# Z05_C8V_03.net
KiCad netlist of a schematic drawn in EAGLE
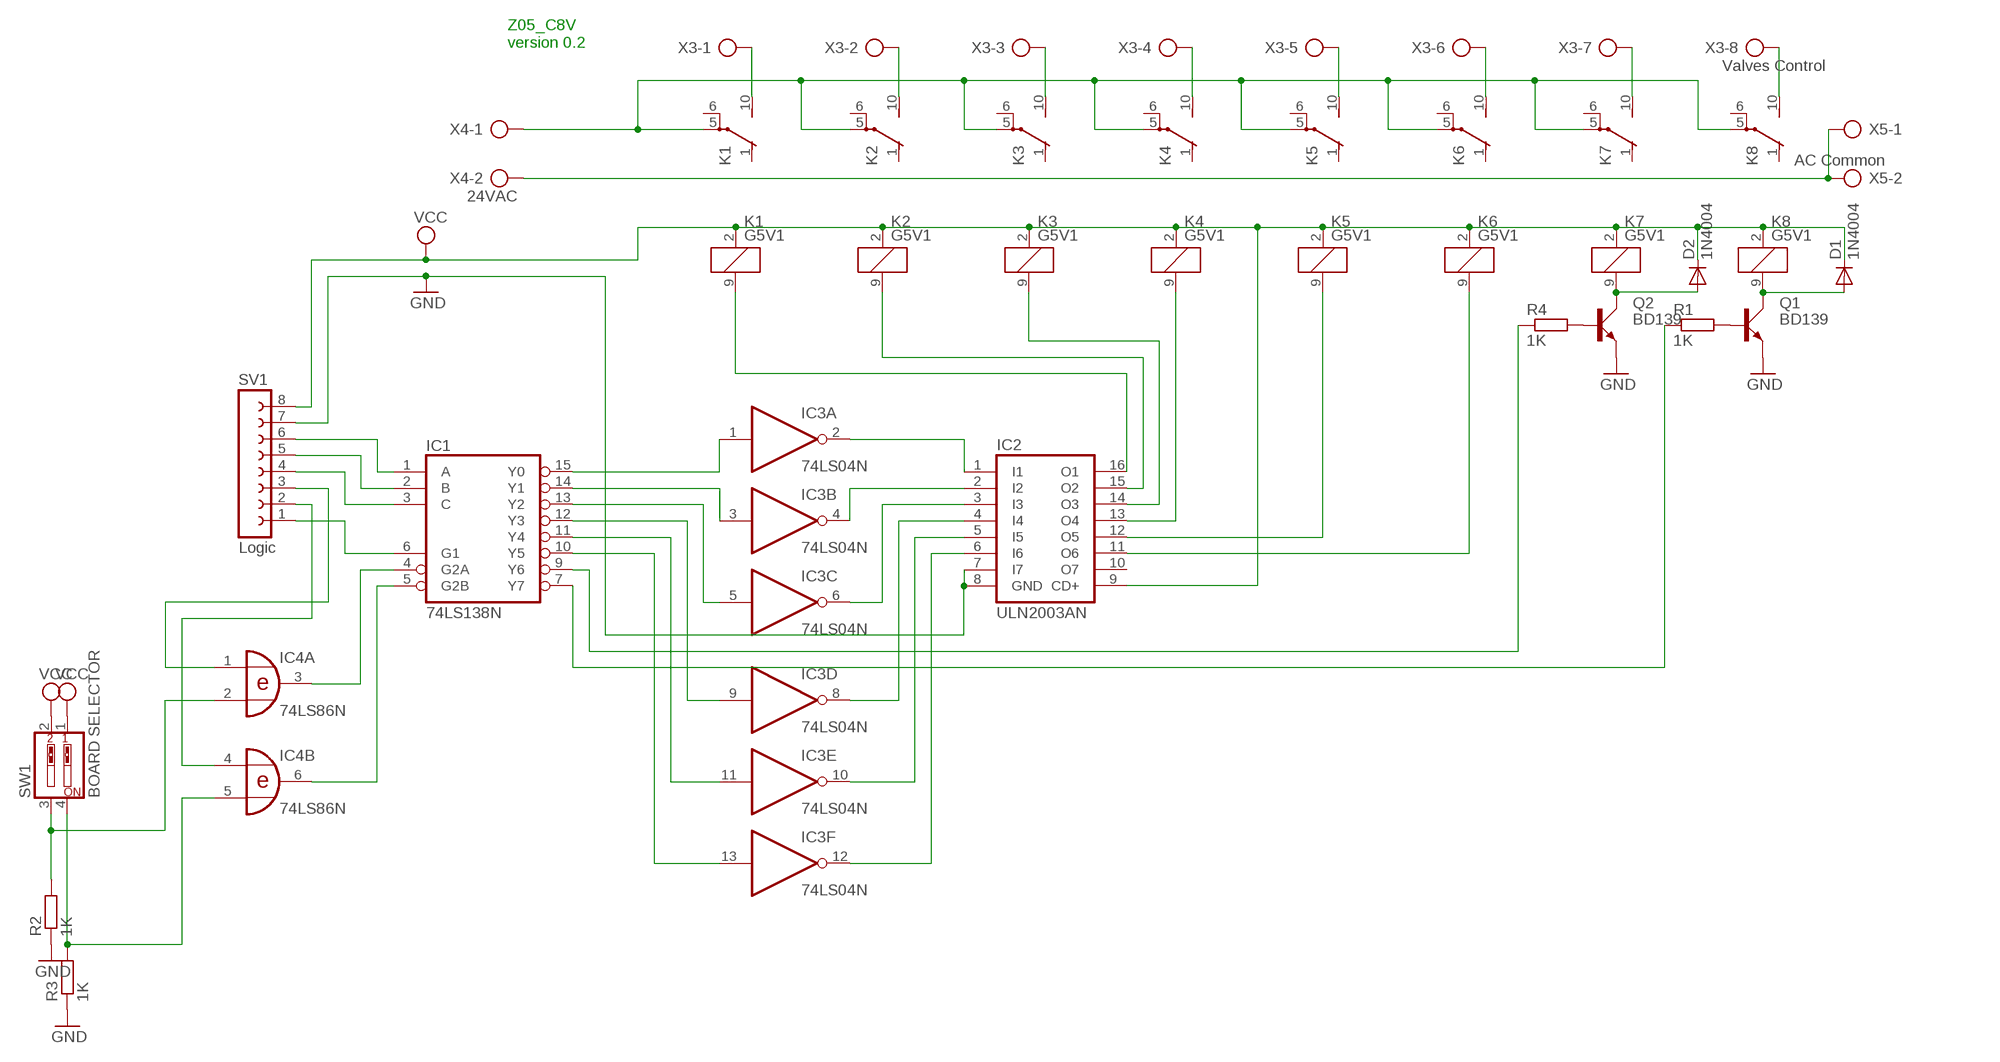
[diagram p0: schematic, sheet 1]

(export (version "E")
  (design (tool "Eeschema 10.0.6"))
  (components
    (comp (ref "D1")
      (value "1N4004")
      (footprint "eagle-import:DO41-10")
      (libsource (lib "eagle-import") (part "1N4004"))
    )
    (comp (ref "D2")
      (value "1N4004")
      (footprint "eagle-import:DO41-10")
      (libsource (lib "eagle-import") (part "1N4004"))
    )
    (comp (ref "IC1")
      (value "74LS138N")
      (footprint "eagle-import:DIL16")
      (libsource (lib "eagle-import") (part "74138NLS"))
    )
    (comp (ref "IC2")
      (value "ULN2003AN")
      (footprint "eagle-import:DIL16")
      (libsource (lib "eagle-import") (part "ULN2003AN"))
    )
    (comp (ref "IC3")
      (value "74LS04N")
      (footprint "eagle-import:DIL14")
      (libsource (lib "eagle-import") (part "7404NLS"))
    )
    (comp (ref "IC4")
      (value "74LS86N")
      (footprint "eagle-import:DIL14")
      (libsource (lib "eagle-import") (part "7486NLS"))
    )
    (comp (ref "K1")
      (value "G5V1")
      (footprint "eagle-import:G5V1")
      (fields (field (name "MPN") "G5V-1-DC24"))
      (libsource (lib "eagle-import") (part "G5V1"))
    )
    (comp (ref "K2")
      (value "G5V1")
      (footprint "eagle-import:G5V1")
      (fields (field (name "MPN") "G5V-1-DC24"))
      (libsource (lib "eagle-import") (part "G5V1"))
    )
    (comp (ref "K3")
      (value "G5V1")
      (footprint "eagle-import:G5V1")
      (fields (field (name "MPN") "G5V-1-DC24"))
      (libsource (lib "eagle-import") (part "G5V1"))
    )
    (comp (ref "K4")
      (value "G5V1")
      (footprint "eagle-import:G5V1")
      (fields (field (name "MPN") "G5V-1-DC24"))
      (libsource (lib "eagle-import") (part "G5V1"))
    )
    (comp (ref "K5")
      (value "G5V1")
      (footprint "eagle-import:G5V1")
      (fields (field (name "MPN") "G5V-1-DC24"))
      (libsource (lib "eagle-import") (part "G5V1"))
    )
    (comp (ref "K6")
      (value "G5V1")
      (footprint "eagle-import:G5V1")
      (fields (field (name "MPN") "G5V-1-DC24"))
      (libsource (lib "eagle-import") (part "G5V1"))
    )
    (comp (ref "K7")
      (value "G5V1")
      (footprint "eagle-import:G5V1")
      (fields (field (name "MPN") "G5V-1-DC24"))
      (libsource (lib "eagle-import") (part "G5V1"))
    )
    (comp (ref "K8")
      (value "G5V1")
      (footprint "eagle-import:G5V1")
      (fields (field (name "MPN") "G5V-1-DC24"))
      (libsource (lib "eagle-import") (part "G5V1"))
    )
    (comp (ref "Q1")
      (value "BD139")
      (footprint "eagle-import:TO126AV")
      (libsource (lib "eagle-import") (part "BD139"))
    )
    (comp (ref "Q2")
      (value "BD139")
      (footprint "eagle-import:TO126AV")
      (libsource (lib "eagle-import") (part "BD139"))
    )
    (comp (ref "R1")
      (value "1K")
      (footprint "eagle-import:0204_7")
      (libsource (lib "eagle-import") (part "R-EU_0204/7"))
    )
    (comp (ref "R2")
      (value "1K")
      (footprint "eagle-import:0204_7")
      (libsource (lib "eagle-import") (part "R-EU_0204/7"))
    )
    (comp (ref "R3")
      (value "1K")
      (footprint "eagle-import:0204_7")
      (libsource (lib "eagle-import") (part "R-EU_0204/7"))
    )
    (comp (ref "R4")
      (value "1K")
      (footprint "eagle-import:0204_7")
      (libsource (lib "eagle-import") (part "R-EU_0204/7"))
    )
    (comp (ref "SV1")
      (value "Logic")
      (footprint "eagle-import:FE08")
      (libsource (lib "eagle-import") (part "FE08-1"))
    )
    (comp (ref "SW1")
      (value "BOARD SELECTOR")
      (footprint "eagle-import:EDG-02")
      (libsource (lib "eagle-import") (part "SW_DIP-2"))
    )
    (comp (ref "X3")
      (value "Valves Control")
      (footprint "eagle-import:AK500_8")
      (libsource (lib "eagle-import") (part "AK500/8"))
    )
    (comp (ref "X4")
      (value "24VAC")
      (footprint "eagle-import:AK500_2")
      (libsource (lib "eagle-import") (part "AK500/2"))
    )
    (comp (ref "X5")
      (value "AC Common")
      (footprint "eagle-import:AK500_2")
      (libsource (lib "eagle-import") (part "AK500/2"))
    )
  )
  (nets
    (net (code "1") (name "GND") (class "Default")
      (node (ref "IC2") (pin "7") (pinfunction "I7_7") (pintype "input"))
      (node (ref "IC2") (pin "8") (pinfunction "GND_8") (pintype "power_in"))
      (node (ref "Q1") (pin "E") (pinfunction "E_E") (pintype "passive"))
      (node (ref "Q2") (pin "E") (pinfunction "E_E") (pintype "passive"))
      (node (ref "R2") (pin "1") (pinfunction "1_1") (pintype "passive"))
      (node (ref "R3") (pin "1") (pinfunction "1_1") (pintype "passive"))
      (node (ref "SV1") (pin "7") (pinfunction "7_7") (pintype "passive"))
    )
    (net (code "2") (name "Net-(IC1A-A)") (class "Default")
      (node (ref "IC1") (pin "1") (pinfunction "A_1") (pintype "input"))
      (node (ref "SV1") (pin "6") (pinfunction "6_6") (pintype "passive"))
    )
    (net (code "3") (name "Net-(IC1A-B)") (class "Default")
      (node (ref "IC1") (pin "2") (pinfunction "B_2") (pintype "input"))
      (node (ref "SV1") (pin "5") (pinfunction "5_5") (pintype "passive"))
    )
    (net (code "4") (name "Net-(IC1A-C)") (class "Default")
      (node (ref "IC1") (pin "3") (pinfunction "C_3") (pintype "input"))
      (node (ref "SV1") (pin "4") (pinfunction "4_4") (pintype "passive"))
    )
    (net (code "5") (name "Net-(IC1A-G1)") (class "Default")
      (node (ref "IC1") (pin "6") (pinfunction "G1_6") (pintype "input"))
      (node (ref "SV1") (pin "1") (pinfunction "1_1") (pintype "passive"))
    )
    (net (code "6") (name "Net-(IC1A-G2A)") (class "Default")
      (node (ref "IC1") (pin "4") (pinfunction "G2A_4") (pintype "input"))
      (node (ref "IC4") (pin "3") (pinfunction "O_3") (pintype "output"))
    )
    (net (code "7") (name "Net-(IC1A-G2B)") (class "Default")
      (node (ref "IC1") (pin "5") (pinfunction "G2B_5") (pintype "input"))
      (node (ref "IC4") (pin "6") (pinfunction "O_6") (pintype "output"))
    )
    (net (code "8") (name "Net-(IC1A-Y0)") (class "Default")
      (node (ref "IC1") (pin "15") (pinfunction "Y0_15") (pintype "output"))
      (node (ref "IC3") (pin "1") (pinfunction "I_1") (pintype "input"))
    )
    (net (code "9") (name "Net-(IC1A-Y1)") (class "Default")
      (node (ref "IC1") (pin "14") (pinfunction "Y1_14") (pintype "output"))
      (node (ref "IC3") (pin "3") (pinfunction "I_3") (pintype "input"))
    )
    (net (code "10") (name "Net-(IC1A-Y2)") (class "Default")
      (node (ref "IC1") (pin "13") (pinfunction "Y2_13") (pintype "output"))
      (node (ref "IC3") (pin "5") (pinfunction "I_5") (pintype "input"))
    )
    (net (code "11") (name "Net-(IC1A-Y3)") (class "Default")
      (node (ref "IC1") (pin "12") (pinfunction "Y3_12") (pintype "output"))
      (node (ref "IC3") (pin "9") (pinfunction "I_9") (pintype "input"))
    )
    (net (code "12") (name "Net-(IC1A-Y4)") (class "Default")
      (node (ref "IC1") (pin "11") (pinfunction "Y4_11") (pintype "output"))
      (node (ref "IC3") (pin "11") (pinfunction "I_11") (pintype "input"))
    )
    (net (code "13") (name "Net-(IC1A-Y5)") (class "Default")
      (node (ref "IC1") (pin "10") (pinfunction "Y5_10") (pintype "output"))
      (node (ref "IC3") (pin "13") (pinfunction "I_13") (pintype "input"))
    )
    (net (code "14") (name "Net-(IC1A-Y6)") (class "Default")
      (node (ref "IC1") (pin "9") (pinfunction "Y6_9") (pintype "output"))
      (node (ref "R4") (pin "1") (pinfunction "1_1") (pintype "passive"))
    )
    (net (code "15") (name "Net-(IC1A-Y7)") (class "Default")
      (node (ref "IC1") (pin "7") (pinfunction "Y7_7") (pintype "output"))
      (node (ref "R1") (pin "1") (pinfunction "1_1") (pintype "passive"))
    )
    (net (code "16") (name "Net-(IC2-I1)") (class "Default")
      (node (ref "IC2") (pin "1") (pinfunction "I1_1") (pintype "input"))
      (node (ref "IC3") (pin "2") (pinfunction "O_2") (pintype "output"))
    )
    (net (code "17") (name "Net-(IC2-I2)") (class "Default")
      (node (ref "IC2") (pin "2") (pinfunction "I2_2") (pintype "input"))
      (node (ref "IC3") (pin "4") (pinfunction "O_4") (pintype "output"))
    )
    (net (code "18") (name "Net-(IC2-I3)") (class "Default")
      (node (ref "IC2") (pin "3") (pinfunction "I3_3") (pintype "input"))
      (node (ref "IC3") (pin "6") (pinfunction "O_6") (pintype "output"))
    )
    (net (code "19") (name "Net-(IC2-I4)") (class "Default")
      (node (ref "IC2") (pin "4") (pinfunction "I4_4") (pintype "input"))
      (node (ref "IC3") (pin "8") (pinfunction "O_8") (pintype "output"))
    )
    (net (code "20") (name "Net-(IC2-I5)") (class "Default")
      (node (ref "IC2") (pin "5") (pinfunction "I5_5") (pintype "input"))
      (node (ref "IC3") (pin "10") (pinfunction "O_10") (pintype "output"))
    )
    (net (code "21") (name "Net-(IC2-I6)") (class "Default")
      (node (ref "IC2") (pin "6") (pinfunction "I6_6") (pintype "input"))
      (node (ref "IC3") (pin "12") (pinfunction "O_12") (pintype "output"))
    )
    (net (code "22") (name "Net-(IC2-O1)") (class "Default")
      (node (ref "IC2") (pin "16") (pinfunction "O1_16") (pintype "open_collector"))
      (node (ref "K1") (pin "9") (pinfunction "2_9") (pintype "passive"))
    )
    (net (code "23") (name "Net-(IC2-O2)") (class "Default")
      (node (ref "IC2") (pin "15") (pinfunction "O2_15") (pintype "open_collector"))
      (node (ref "K2") (pin "9") (pinfunction "2_9") (pintype "passive"))
    )
    (net (code "24") (name "Net-(IC2-O3)") (class "Default")
      (node (ref "IC2") (pin "14") (pinfunction "O3_14") (pintype "open_collector"))
      (node (ref "K3") (pin "9") (pinfunction "2_9") (pintype "passive"))
    )
    (net (code "25") (name "Net-(IC2-O4)") (class "Default")
      (node (ref "IC2") (pin "13") (pinfunction "O4_13") (pintype "open_collector"))
      (node (ref "K4") (pin "9") (pinfunction "2_9") (pintype "passive"))
    )
    (net (code "26") (name "Net-(IC2-O5)") (class "Default")
      (node (ref "IC2") (pin "12") (pinfunction "O5_12") (pintype "open_collector"))
      (node (ref "K5") (pin "9") (pinfunction "2_9") (pintype "passive"))
    )
    (net (code "27") (name "Net-(IC2-O6)") (class "Default")
      (node (ref "IC2") (pin "11") (pinfunction "O6_11") (pintype "open_collector"))
      (node (ref "K6") (pin "9") (pinfunction "2_9") (pintype "passive"))
    )
    (net (code "28") (name "Net-(IC4A-I0)") (class "Default")
      (node (ref "IC4") (pin "1") (pinfunction "I0_1") (pintype "input"))
      (node (ref "SV1") (pin "3") (pinfunction "3_3") (pintype "passive"))
    )
    (net (code "29") (name "Net-(IC4A-I1)") (class "Default")
      (node (ref "IC4") (pin "2") (pinfunction "I1_2") (pintype "input"))
      (node (ref "R2") (pin "2") (pinfunction "2_2") (pintype "passive"))
      (node (ref "SW1") (pin "3") (pinfunction "3_3") (pintype "passive"))
    )
    (net (code "30") (name "Net-(IC4B-I0)") (class "Default")
      (node (ref "IC4") (pin "4") (pinfunction "I0_4") (pintype "input"))
      (node (ref "SV1") (pin "2") (pinfunction "2_2") (pintype "passive"))
    )
    (net (code "31") (name "Net-(IC4B-I1)") (class "Default")
      (node (ref "IC4") (pin "5") (pinfunction "I1_5") (pintype "input"))
      (node (ref "R3") (pin "2") (pinfunction "2_2") (pintype "passive"))
      (node (ref "SW1") (pin "4") (pinfunction "4_4") (pintype "passive"))
    )
    (net (code "32") (name "Net-(K1B-S)") (class "Default")
      (node (ref "K1") (pin "10") (pinfunction "S_10") (pintype "passive"))
      (node (ref "X3") (pin "1") (pinfunction "KL_1") (pintype "passive"))
    )
    (net (code "33") (name "Net-(K2B-S)") (class "Default")
      (node (ref "K2") (pin "10") (pinfunction "S_10") (pintype "passive"))
      (node (ref "X3") (pin "2") (pinfunction "KL_2") (pintype "passive"))
    )
    (net (code "34") (name "Net-(K3B-S)") (class "Default")
      (node (ref "K3") (pin "10") (pinfunction "S_10") (pintype "passive"))
      (node (ref "X3") (pin "3") (pinfunction "KL_3") (pintype "passive"))
    )
    (net (code "35") (name "Net-(K4B-S)") (class "Default")
      (node (ref "K4") (pin "10") (pinfunction "S_10") (pintype "passive"))
      (node (ref "X3") (pin "4") (pinfunction "KL_4") (pintype "passive"))
    )
    (net (code "36") (name "Net-(K5B-S)") (class "Default")
      (node (ref "K5") (pin "10") (pinfunction "S_10") (pintype "passive"))
      (node (ref "X3") (pin "5") (pinfunction "KL_5") (pintype "passive"))
    )
    (net (code "37") (name "Net-(K6B-S)") (class "Default")
      (node (ref "K6") (pin "10") (pinfunction "S_10") (pintype "passive"))
      (node (ref "X3") (pin "6") (pinfunction "KL_6") (pintype "passive"))
    )
    (net (code "38") (name "Net-(K7A-2)") (class "Default")
      (node (ref "D2") (pin "A") (pinfunction "A_A") (pintype "passive"))
      (node (ref "K7") (pin "9") (pinfunction "2_9") (pintype "passive"))
      (node (ref "Q2") (pin "C") (pinfunction "C_C") (pintype "passive"))
    )
    (net (code "39") (name "Net-(K7B-S)") (class "Default")
      (node (ref "K7") (pin "10") (pinfunction "S_10") (pintype "passive"))
      (node (ref "X3") (pin "7") (pinfunction "KL_7") (pintype "passive"))
    )
    (net (code "40") (name "Net-(K8A-2)") (class "Default")
      (node (ref "D1") (pin "A") (pinfunction "A_A") (pintype "passive"))
      (node (ref "K8") (pin "9") (pinfunction "2_9") (pintype "passive"))
      (node (ref "Q1") (pin "C") (pinfunction "C_C") (pintype "passive"))
    )
    (net (code "41") (name "Net-(K8B-S)") (class "Default")
      (node (ref "K8") (pin "10") (pinfunction "S_10") (pintype "passive"))
      (node (ref "X3") (pin "8") (pinfunction "KL_8") (pintype "passive"))
    )
    (net (code "42") (name "Net-(Q1-PadB)") (class "Default")
      (node (ref "Q1") (pin "B") (pinfunction "B_B") (pintype "passive"))
      (node (ref "R1") (pin "2") (pinfunction "2_2") (pintype "passive"))
    )
    (net (code "43") (name "Net-(Q2-PadB)") (class "Default")
      (node (ref "Q2") (pin "B") (pinfunction "B_B") (pintype "passive"))
      (node (ref "R4") (pin "2") (pinfunction "2_2") (pintype "passive"))
    )
    (net (code "44") (name "Net-(X4A-KL)") (class "Default")
      (node (ref "K1") (pin "5") (pinfunction "P_5") (pintype "passive"))
      (node (ref "K2") (pin "5") (pinfunction "P_5") (pintype "passive"))
      (node (ref "K3") (pin "5") (pinfunction "P_5") (pintype "passive"))
      (node (ref "K4") (pin "5") (pinfunction "P_5") (pintype "passive"))
      (node (ref "K5") (pin "5") (pinfunction "P_5") (pintype "passive"))
      (node (ref "K6") (pin "5") (pinfunction "P_5") (pintype "passive"))
      (node (ref "K7") (pin "5") (pinfunction "P_5") (pintype "passive"))
      (node (ref "K8") (pin "5") (pinfunction "P_5") (pintype "passive"))
      (node (ref "X4") (pin "1") (pinfunction "KL_1") (pintype "passive"))
    )
    (net (code "45") (name "Net-(X4B-KL)") (class "Default")
      (node (ref "X4") (pin "2") (pinfunction "KL_2") (pintype "passive"))
      (node (ref "X5") (pin "1") (pinfunction "KL_1") (pintype "passive"))
      (node (ref "X5") (pin "2") (pinfunction "KL_2") (pintype "passive"))
    )
    (net (code "46") (name "VCC") (class "Default")
      (node (ref "D1") (pin "C") (pinfunction "C_C") (pintype "passive"))
      (node (ref "D2") (pin "C") (pinfunction "C_C") (pintype "passive"))
      (node (ref "IC2") (pin "9") (pinfunction "CD+_9") (pintype "passive"))
      (node (ref "K1") (pin "2") (pinfunction "1_2") (pintype "passive"))
      (node (ref "K2") (pin "2") (pinfunction "1_2") (pintype "passive"))
      (node (ref "K3") (pin "2") (pinfunction "1_2") (pintype "passive"))
      (node (ref "K4") (pin "2") (pinfunction "1_2") (pintype "passive"))
      (node (ref "K5") (pin "2") (pinfunction "1_2") (pintype "passive"))
      (node (ref "K6") (pin "2") (pinfunction "1_2") (pintype "passive"))
      (node (ref "K7") (pin "2") (pinfunction "1_2") (pintype "passive"))
      (node (ref "K8") (pin "2") (pinfunction "1_2") (pintype "passive"))
      (node (ref "SV1") (pin "8") (pinfunction "8_8") (pintype "passive"))
      (node (ref "SW1") (pin "1") (pinfunction "1_1") (pintype "passive"))
      (node (ref "SW1") (pin "2") (pinfunction "2_2") (pintype "passive"))
    )
    (net (code "47") (name "unconnected-(IC2-O7-Pad10)") (class "Default")
      (node (ref "IC2") (pin "10") (pinfunction "O7_10") (pintype "open_collector"))
    )
    (net (code "48") (name "unconnected-(K1B-O-Pad1)") (class "Default")
      (node (ref "K1") (pin "1") (pinfunction "O_1") (pintype "passive"))
    )
    (net (code "49") (name "unconnected-(K1B-P-Pad6)") (class "Default")
      (node (ref "K1") (pin "6") (pinfunction "P_6") (pintype "passive"))
    )
    (net (code "50") (name "unconnected-(K2B-O-Pad1)") (class "Default")
      (node (ref "K2") (pin "1") (pinfunction "O_1") (pintype "passive"))
    )
    (net (code "51") (name "unconnected-(K2B-P-Pad6)") (class "Default")
      (node (ref "K2") (pin "6") (pinfunction "P_6") (pintype "passive"))
    )
    (net (code "52") (name "unconnected-(K3B-O-Pad1)") (class "Default")
      (node (ref "K3") (pin "1") (pinfunction "O_1") (pintype "passive"))
    )
    (net (code "53") (name "unconnected-(K3B-P-Pad6)") (class "Default")
      (node (ref "K3") (pin "6") (pinfunction "P_6") (pintype "passive"))
    )
    (net (code "54") (name "unconnected-(K4B-O-Pad1)") (class "Default")
      (node (ref "K4") (pin "1") (pinfunction "O_1") (pintype "passive"))
    )
    (net (code "55") (name "unconnected-(K4B-P-Pad6)") (class "Default")
      (node (ref "K4") (pin "6") (pinfunction "P_6") (pintype "passive"))
    )
    (net (code "56") (name "unconnected-(K5B-O-Pad1)") (class "Default")
      (node (ref "K5") (pin "1") (pinfunction "O_1") (pintype "passive"))
    )
    (net (code "57") (name "unconnected-(K5B-P-Pad6)") (class "Default")
      (node (ref "K5") (pin "6") (pinfunction "P_6") (pintype "passive"))
    )
    (net (code "58") (name "unconnected-(K6B-O-Pad1)") (class "Default")
      (node (ref "K6") (pin "1") (pinfunction "O_1") (pintype "passive"))
    )
    (net (code "59") (name "unconnected-(K6B-P-Pad6)") (class "Default")
      (node (ref "K6") (pin "6") (pinfunction "P_6") (pintype "passive"))
    )
    (net (code "60") (name "unconnected-(K7B-O-Pad1)") (class "Default")
      (node (ref "K7") (pin "1") (pinfunction "O_1") (pintype "passive"))
    )
    (net (code "61") (name "unconnected-(K7B-P-Pad6)") (class "Default")
      (node (ref "K7") (pin "6") (pinfunction "P_6") (pintype "passive"))
    )
    (net (code "62") (name "unconnected-(K8B-O-Pad1)") (class "Default")
      (node (ref "K8") (pin "1") (pinfunction "O_1") (pintype "passive"))
    )
    (net (code "63") (name "unconnected-(K8B-P-Pad6)") (class "Default")
      (node (ref "K8") (pin "6") (pinfunction "P_6") (pintype "passive"))
    )
  )
)
